# assr.net
KiCad netlist of a schematic drawn in EAGLE
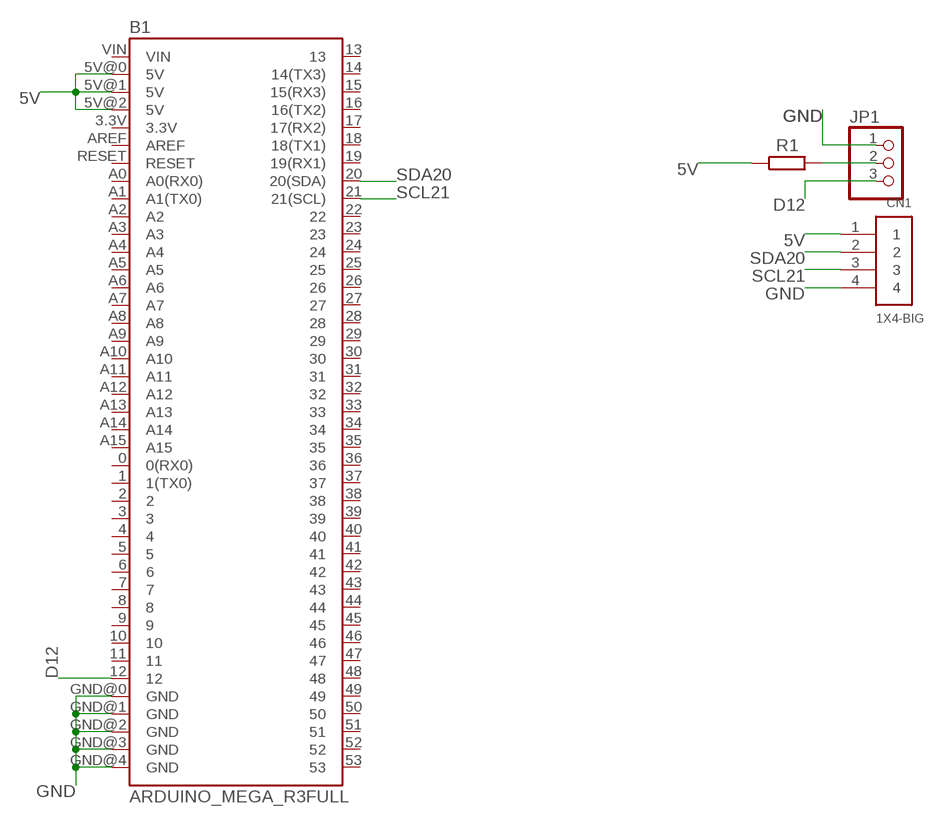
[diagram p0: schematic, sheet 1]

(export (version "E")
  (design (tool "Eeschema 10.0.6"))
  (components
    (comp (ref "B1")
      (value "ARDUINO_MEGA_R3FULL")
      (footprint "eagle-import:ARDUINO_MEGA")
      (libsource (lib "eagle-import") (part "ARDUINO_MEGA_R3FULL"))
    )
    (comp (ref "CN1")
      (value "1X4-BIG")
      (footprint "eagle-import:1X04-BIG")
      (libsource (lib "eagle-import") (part "1X4-BIG"))
    )
    (comp (ref "JP1")
      (value "PINHD-1X3CB")
      (footprint "eagle-import:1X03-CLEANBIG")
      (libsource (lib "eagle-import") (part "PINHD-1X3CB"))
    )
    (comp (ref "R1")
      (value "R_AXIAL-11.7MM-PITCH")
      (footprint "eagle-import:RESAD1176W63L850D250B")
      (libsource (lib "eagle-import") (part "RAXIAL-11.7MM-PITCH_"))
    )
  )
  (nets
    (net (code "1") (name "/5V") (class "Default")
      (node (ref "B1") (pin "5V@0") (pinfunction "5V_5V@0") (pintype "bidirectional"))
      (node (ref "B1") (pin "5V@1") (pinfunction "5V_5V@1") (pintype "bidirectional"))
      (node (ref "B1") (pin "5V@2") (pinfunction "5V_5V@2") (pintype "bidirectional"))
      (node (ref "CN1") (pin "1") (pinfunction "1_1") (pintype "bidirectional"))
      (node (ref "R1") (pin "1") (pinfunction "1_1") (pintype "passive"))
    )
    (net (code "2") (name "/D12") (class "Default")
      (node (ref "B1") (pin "12") (pinfunction "12_12") (pintype "bidirectional"))
      (node (ref "JP1") (pin "3") (pinfunction "3_3") (pintype "passive"))
    )
    (net (code "3") (name "/GND") (class "Default")
      (node (ref "B1") (pin "GND@0") (pinfunction "GND_GND@0") (pintype "bidirectional"))
      (node (ref "B1") (pin "GND@1") (pinfunction "GND_GND@1") (pintype "bidirectional"))
      (node (ref "B1") (pin "GND@2") (pinfunction "GND_GND@2") (pintype "bidirectional"))
      (node (ref "B1") (pin "GND@3") (pinfunction "GND_GND@3") (pintype "bidirectional"))
      (node (ref "B1") (pin "GND@4") (pinfunction "GND_GND@4") (pintype "bidirectional"))
      (node (ref "CN1") (pin "4") (pinfunction "4_4") (pintype "bidirectional"))
      (node (ref "JP1") (pin "1") (pinfunction "1_1") (pintype "passive"))
    )
    (net (code "4") (name "/SCL21") (class "Default")
      (node (ref "B1") (pin "21") (pinfunction "21(SCL)_21") (pintype "bidirectional"))
      (node (ref "CN1") (pin "3") (pinfunction "3_3") (pintype "bidirectional"))
    )
    (net (code "5") (name "/SDA20") (class "Default")
      (node (ref "B1") (pin "20") (pinfunction "20(SDA)_20") (pintype "bidirectional"))
      (node (ref "CN1") (pin "2") (pinfunction "2_2") (pintype "bidirectional"))
    )
    (net (code "6") (name "Net-(JP1-Pad2)") (class "Default")
      (node (ref "JP1") (pin "2") (pinfunction "2_2") (pintype "passive"))
      (node (ref "R1") (pin "2") (pinfunction "2_2") (pintype "passive"))
    )
    (net (code "7") (name "unconnected-(B1-0(RX0)-Pad0)") (class "Default")
      (node (ref "B1") (pin "0") (pinfunction "0(RX0)_0") (pintype "bidirectional"))
    )
    (net (code "8") (name "unconnected-(B1-1(TX0)-Pad1)") (class "Default")
      (node (ref "B1") (pin "1") (pinfunction "1(TX0)_1") (pintype "bidirectional"))
    )
    (net (code "9") (name "unconnected-(B1-14(TX3)-Pad14)") (class "Default")
      (node (ref "B1") (pin "14") (pinfunction "14(TX3)_14") (pintype "bidirectional"))
    )
    (net (code "10") (name "unconnected-(B1-15(RX3)-Pad15)") (class "Default")
      (node (ref "B1") (pin "15") (pinfunction "15(RX3)_15") (pintype "bidirectional"))
    )
    (net (code "11") (name "unconnected-(B1-16(TX2)-Pad16)") (class "Default")
      (node (ref "B1") (pin "16") (pinfunction "16(TX2)_16") (pintype "bidirectional"))
    )
    (net (code "12") (name "unconnected-(B1-17(RX2)-Pad17)") (class "Default")
      (node (ref "B1") (pin "17") (pinfunction "17(RX2)_17") (pintype "bidirectional"))
    )
    (net (code "13") (name "unconnected-(B1-18(TX1)-Pad18)") (class "Default")
      (node (ref "B1") (pin "18") (pinfunction "18(TX1)_18") (pintype "bidirectional"))
    )
    (net (code "14") (name "unconnected-(B1-19(RX1)-Pad19)") (class "Default")
      (node (ref "B1") (pin "19") (pinfunction "19(RX1)_19") (pintype "bidirectional"))
    )
    (net (code "15") (name "unconnected-(B1-A0(RX0)-PadA0)") (class "Default")
      (node (ref "B1") (pin "A0") (pinfunction "A0(RX0)_A0") (pintype "bidirectional"))
    )
    (net (code "16") (name "unconnected-(B1-A1(TX0)-PadA1)") (class "Default")
      (node (ref "B1") (pin "A1") (pinfunction "A1(TX0)_A1") (pintype "bidirectional"))
    )
    (net (code "17") (name "unconnected-(B1-Pad2)") (class "Default")
      (node (ref "B1") (pin "2") (pinfunction "2_2") (pintype "bidirectional"))
    )
    (net (code "18") (name "unconnected-(B1-Pad3)") (class "Default")
      (node (ref "B1") (pin "3") (pinfunction "3_3") (pintype "bidirectional"))
    )
    (net (code "19") (name "unconnected-(B1-Pad3.3V)") (class "Default")
      (node (ref "B1") (pin "3.3V") (pinfunction "3.3V_3.3V") (pintype "bidirectional"))
    )
    (net (code "20") (name "unconnected-(B1-Pad4)") (class "Default")
      (node (ref "B1") (pin "4") (pinfunction "4_4") (pintype "bidirectional"))
    )
    (net (code "21") (name "unconnected-(B1-Pad5)") (class "Default")
      (node (ref "B1") (pin "5") (pinfunction "5_5") (pintype "bidirectional"))
    )
    (net (code "22") (name "unconnected-(B1-Pad6)") (class "Default")
      (node (ref "B1") (pin "6") (pinfunction "6_6") (pintype "bidirectional"))
    )
    (net (code "23") (name "unconnected-(B1-Pad7)") (class "Default")
      (node (ref "B1") (pin "7") (pinfunction "7_7") (pintype "bidirectional"))
    )
    (net (code "24") (name "unconnected-(B1-Pad8)") (class "Default")
      (node (ref "B1") (pin "8") (pinfunction "8_8") (pintype "bidirectional"))
    )
    (net (code "25") (name "unconnected-(B1-Pad9)") (class "Default")
      (node (ref "B1") (pin "9") (pinfunction "9_9") (pintype "bidirectional"))
    )
    (net (code "26") (name "unconnected-(B1-Pad10)") (class "Default")
      (node (ref "B1") (pin "10") (pinfunction "10_10") (pintype "bidirectional"))
    )
    (net (code "27") (name "unconnected-(B1-Pad11)") (class "Default")
      (node (ref "B1") (pin "11") (pinfunction "11_11") (pintype "bidirectional"))
    )
    (net (code "28") (name "unconnected-(B1-Pad13)") (class "Default")
      (node (ref "B1") (pin "13") (pinfunction "13_13") (pintype "bidirectional"))
    )
    (net (code "29") (name "unconnected-(B1-Pad22)") (class "Default")
      (node (ref "B1") (pin "22") (pinfunction "22_22") (pintype "bidirectional"))
    )
    (net (code "30") (name "unconnected-(B1-Pad23)") (class "Default")
      (node (ref "B1") (pin "23") (pinfunction "23_23") (pintype "bidirectional"))
    )
    (net (code "31") (name "unconnected-(B1-Pad24)") (class "Default")
      (node (ref "B1") (pin "24") (pinfunction "24_24") (pintype "bidirectional"))
    )
    (net (code "32") (name "unconnected-(B1-Pad25)") (class "Default")
      (node (ref "B1") (pin "25") (pinfunction "25_25") (pintype "bidirectional"))
    )
    (net (code "33") (name "unconnected-(B1-Pad26)") (class "Default")
      (node (ref "B1") (pin "26") (pinfunction "26_26") (pintype "bidirectional"))
    )
    (net (code "34") (name "unconnected-(B1-Pad27)") (class "Default")
      (node (ref "B1") (pin "27") (pinfunction "27_27") (pintype "bidirectional"))
    )
    (net (code "35") (name "unconnected-(B1-Pad28)") (class "Default")
      (node (ref "B1") (pin "28") (pinfunction "28_28") (pintype "bidirectional"))
    )
    (net (code "36") (name "unconnected-(B1-Pad29)") (class "Default")
      (node (ref "B1") (pin "29") (pinfunction "29_29") (pintype "bidirectional"))
    )
    (net (code "37") (name "unconnected-(B1-Pad30)") (class "Default")
      (node (ref "B1") (pin "30") (pinfunction "30_30") (pintype "bidirectional"))
    )
    (net (code "38") (name "unconnected-(B1-Pad31)") (class "Default")
      (node (ref "B1") (pin "31") (pinfunction "31_31") (pintype "bidirectional"))
    )
    (net (code "39") (name "unconnected-(B1-Pad32)") (class "Default")
      (node (ref "B1") (pin "32") (pinfunction "32_32") (pintype "bidirectional"))
    )
    (net (code "40") (name "unconnected-(B1-Pad33)") (class "Default")
      (node (ref "B1") (pin "33") (pinfunction "33_33") (pintype "bidirectional"))
    )
    (net (code "41") (name "unconnected-(B1-Pad34)") (class "Default")
      (node (ref "B1") (pin "34") (pinfunction "34_34") (pintype "bidirectional"))
    )
    (net (code "42") (name "unconnected-(B1-Pad35)") (class "Default")
      (node (ref "B1") (pin "35") (pinfunction "35_35") (pintype "bidirectional"))
    )
    (net (code "43") (name "unconnected-(B1-Pad36)") (class "Default")
      (node (ref "B1") (pin "36") (pinfunction "36_36") (pintype "bidirectional"))
    )
    (net (code "44") (name "unconnected-(B1-Pad37)") (class "Default")
      (node (ref "B1") (pin "37") (pinfunction "37_37") (pintype "bidirectional"))
    )
    (net (code "45") (name "unconnected-(B1-Pad38)") (class "Default")
      (node (ref "B1") (pin "38") (pinfunction "38_38") (pintype "bidirectional"))
    )
    (net (code "46") (name "unconnected-(B1-Pad39)") (class "Default")
      (node (ref "B1") (pin "39") (pinfunction "39_39") (pintype "bidirectional"))
    )
    (net (code "47") (name "unconnected-(B1-Pad40)") (class "Default")
      (node (ref "B1") (pin "40") (pinfunction "40_40") (pintype "bidirectional"))
    )
    (net (code "48") (name "unconnected-(B1-Pad41)") (class "Default")
      (node (ref "B1") (pin "41") (pinfunction "41_41") (pintype "bidirectional"))
    )
    (net (code "49") (name "unconnected-(B1-Pad42)") (class "Default")
      (node (ref "B1") (pin "42") (pinfunction "42_42") (pintype "bidirectional"))
    )
    (net (code "50") (name "unconnected-(B1-Pad43)") (class "Default")
      (node (ref "B1") (pin "43") (pinfunction "43_43") (pintype "bidirectional"))
    )
    (net (code "51") (name "unconnected-(B1-Pad44)") (class "Default")
      (node (ref "B1") (pin "44") (pinfunction "44_44") (pintype "bidirectional"))
    )
    (net (code "52") (name "unconnected-(B1-Pad45)") (class "Default")
      (node (ref "B1") (pin "45") (pinfunction "45_45") (pintype "bidirectional"))
    )
    (net (code "53") (name "unconnected-(B1-Pad46)") (class "Default")
      (node (ref "B1") (pin "46") (pinfunction "46_46") (pintype "bidirectional"))
    )
    (net (code "54") (name "unconnected-(B1-Pad47)") (class "Default")
      (node (ref "B1") (pin "47") (pinfunction "47_47") (pintype "bidirectional"))
    )
    (net (code "55") (name "unconnected-(B1-Pad48)") (class "Default")
      (node (ref "B1") (pin "48") (pinfunction "48_48") (pintype "bidirectional"))
    )
    (net (code "56") (name "unconnected-(B1-Pad49)") (class "Default")
      (node (ref "B1") (pin "49") (pinfunction "49_49") (pintype "bidirectional"))
    )
    (net (code "57") (name "unconnected-(B1-Pad50)") (class "Default")
      (node (ref "B1") (pin "50") (pinfunction "50_50") (pintype "bidirectional"))
    )
    (net (code "58") (name "unconnected-(B1-Pad51)") (class "Default")
      (node (ref "B1") (pin "51") (pinfunction "51_51") (pintype "bidirectional"))
    )
    (net (code "59") (name "unconnected-(B1-Pad52)") (class "Default")
      (node (ref "B1") (pin "52") (pinfunction "52_52") (pintype "bidirectional"))
    )
    (net (code "60") (name "unconnected-(B1-Pad53)") (class "Default")
      (node (ref "B1") (pin "53") (pinfunction "53_53") (pintype "bidirectional"))
    )
    (net (code "61") (name "unconnected-(B1-PadA2)") (class "Default")
      (node (ref "B1") (pin "A2") (pinfunction "A2_A2") (pintype "bidirectional"))
    )
    (net (code "62") (name "unconnected-(B1-PadA3)") (class "Default")
      (node (ref "B1") (pin "A3") (pinfunction "A3_A3") (pintype "bidirectional"))
    )
    (net (code "63") (name "unconnected-(B1-PadA4)") (class "Default")
      (node (ref "B1") (pin "A4") (pinfunction "A4_A4") (pintype "bidirectional"))
    )
    (net (code "64") (name "unconnected-(B1-PadA5)") (class "Default")
      (node (ref "B1") (pin "A5") (pinfunction "A5_A5") (pintype "bidirectional"))
    )
    (net (code "65") (name "unconnected-(B1-PadA6)") (class "Default")
      (node (ref "B1") (pin "A6") (pinfunction "A6_A6") (pintype "bidirectional"))
    )
    (net (code "66") (name "unconnected-(B1-PadA7)") (class "Default")
      (node (ref "B1") (pin "A7") (pinfunction "A7_A7") (pintype "bidirectional"))
    )
    (net (code "67") (name "unconnected-(B1-PadA8)") (class "Default")
      (node (ref "B1") (pin "A8") (pinfunction "A8_A8") (pintype "bidirectional"))
    )
    (net (code "68") (name "unconnected-(B1-PadA9)") (class "Default")
      (node (ref "B1") (pin "A9") (pinfunction "A9_A9") (pintype "bidirectional"))
    )
    (net (code "69") (name "unconnected-(B1-PadA10)") (class "Default")
      (node (ref "B1") (pin "A10") (pinfunction "A10_A10") (pintype "bidirectional"))
    )
    (net (code "70") (name "unconnected-(B1-PadA11)") (class "Default")
      (node (ref "B1") (pin "A11") (pinfunction "A11_A11") (pintype "bidirectional"))
    )
    (net (code "71") (name "unconnected-(B1-PadA12)") (class "Default")
      (node (ref "B1") (pin "A12") (pinfunction "A12_A12") (pintype "bidirectional"))
    )
    (net (code "72") (name "unconnected-(B1-PadA13)") (class "Default")
      (node (ref "B1") (pin "A13") (pinfunction "A13_A13") (pintype "bidirectional"))
    )
    (net (code "73") (name "unconnected-(B1-PadA14)") (class "Default")
      (node (ref "B1") (pin "A14") (pinfunction "A14_A14") (pintype "bidirectional"))
    )
    (net (code "74") (name "unconnected-(B1-PadA15)") (class "Default")
      (node (ref "B1") (pin "A15") (pinfunction "A15_A15") (pintype "bidirectional"))
    )
    (net (code "75") (name "unconnected-(B1-PadAREF)") (class "Default")
      (node (ref "B1") (pin "AREF") (pinfunction "AREF_AREF") (pintype "bidirectional"))
    )
    (net (code "76") (name "unconnected-(B1-PadRESET)") (class "Default")
      (node (ref "B1") (pin "RESET") (pinfunction "RESET_RESET") (pintype "bidirectional"))
    )
    (net (code "77") (name "unconnected-(B1-PadVIN)") (class "Default")
      (node (ref "B1") (pin "VIN") (pinfunction "VIN_VIN") (pintype "bidirectional"))
    )
  )
)
